# yetisponder_vesp02_2_2.net
KiCad netlist of a schematic drawn in EAGLE
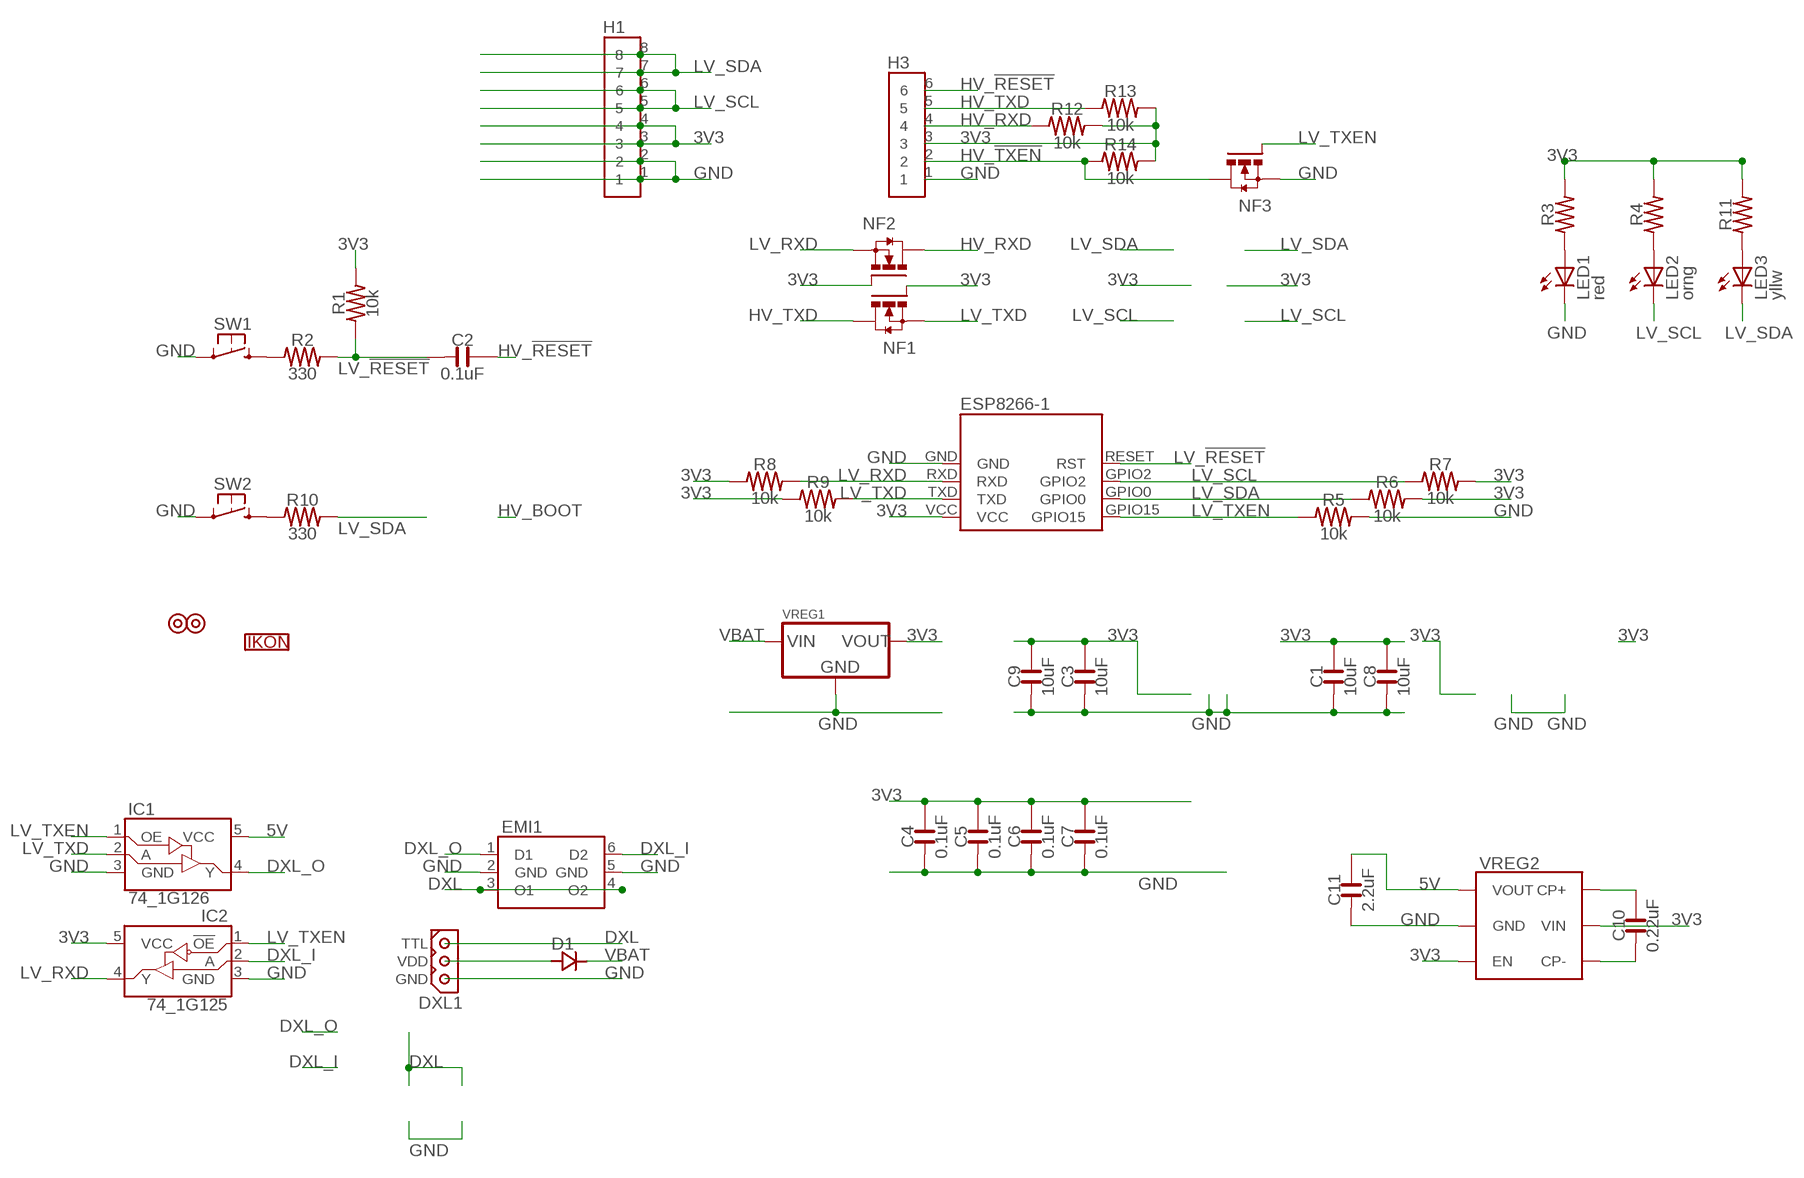
[diagram p0: schematic, sheet 1]

(export (version "E")
  (design (tool "Eeschema 10.0.6"))
  (components
    (comp (ref "C1")
      (value "10uF")
      (footprint "eagle-import:0805_YAGEO")
      (libsource (lib "eagle-import") (part "CAPACITOR-0805"))
    )
    (comp (ref "C2")
      (value "0.1uF")
      (footprint "eagle-import:0402_YAGEO")
      (libsource (lib "eagle-import") (part "CAPACITOR-0402"))
    )
    (comp (ref "C3")
      (value "10uF")
      (footprint "eagle-import:0805_YAGEO")
      (libsource (lib "eagle-import") (part "CAPACITOR-0805"))
    )
    (comp (ref "C4")
      (value "0.1uF")
      (footprint "eagle-import:0402_YAGEO")
      (libsource (lib "eagle-import") (part "CAPACITOR-0402"))
    )
    (comp (ref "C5")
      (value "0.1uF")
      (footprint "eagle-import:0402_YAGEO")
      (libsource (lib "eagle-import") (part "CAPACITOR-0402"))
    )
    (comp (ref "C6")
      (value "0.1uF")
      (footprint "eagle-import:0402_YAGEO")
      (libsource (lib "eagle-import") (part "CAPACITOR-0402"))
    )
    (comp (ref "C7")
      (value "0.1uF")
      (footprint "eagle-import:0402_YAGEO")
      (libsource (lib "eagle-import") (part "CAPACITOR-0402"))
    )
    (comp (ref "C8")
      (value "10uF")
      (footprint "eagle-import:0805_YAGEO")
      (libsource (lib "eagle-import") (part "CAPACITOR-0805"))
    )
    (comp (ref "C9")
      (value "10uF")
      (footprint "eagle-import:0805_YAGEO")
      (libsource (lib "eagle-import") (part "CAPACITOR-0805"))
    )
    (comp (ref "C10")
      (value "0.22uF")
      (footprint "eagle-import:0402_YAGEO")
      (libsource (lib "eagle-import") (part "CAPACITOR-0402"))
    )
    (comp (ref "C11")
      (value "2.2uF")
      (footprint "eagle-import:0402_YAGEO")
      (libsource (lib "eagle-import") (part "CAPACITOR-0402"))
    )
    (comp (ref "D1")
      (value "DIODE_RECTIFIER-POWER-DI5")
      (footprint "eagle-import:POWER-DI5")
      (libsource (lib "eagle-import") (part "DIODE_RECTIFIER-POWER-DI5"))
    )
    (comp (ref "DXL1")
      (value "DXL_TTL-V")
      (footprint "eagle-import:MOLEX_5267-3")
      (libsource (lib "eagle-import") (part "DXL_TTL-V"))
    )
    (comp (ref "EMI1")
      (value "EMI_2CH")
      (footprint "eagle-import:SOT-563")
      (libsource (lib "eagle-import") (part "EMI_2CH"))
    )
    (comp (ref "ESP8266-1")
      (value "ESP8266-02")
      (footprint "eagle-import:ESP8266-02")
      (libsource (lib "eagle-import") (part "ESP8266-02"))
    )
    (comp (ref "H1")
      (value "HEADER_8P-0.1\"_2X4-SMD-SULLINS")
      (footprint "eagle-import:HEADER-0.1__2X4-SMD-SULLINS")
      (libsource (lib "eagle-import") (part "HEADER_8P-0.1{dblquote}_2X4-SMD-SULLINS"))
    )
    (comp (ref "H3")
      (value "HEADER_6P-0.1\"")
      (footprint "eagle-import:HEADER-0.1__1X6")
      (libsource (lib "eagle-import") (part "HEADER_6P-0.1{dblquote}"))
    )
    (comp (ref "IC1")
      (value "LOGIC_74_1G126-DCK")
      (footprint "eagle-import:DCK(R-PDSO-G5)_SC70")
      (libsource (lib "eagle-import") (part "LOGIC_74_1G126-DCK"))
    )
    (comp (ref "IC2")
      (value "LOGIC_74_1G125-DCK")
      (footprint "eagle-import:DCK(R-PDSO-G5)_SC70")
      (libsource (lib "eagle-import") (part "LOGIC_74_1G125-DCK"))
    )
    (comp (ref "IKON1")
      (value "IKON-VERSACOMA-5")
      (footprint "eagle-import:IKON_VERSACOMA_5MM")
      (libsource (lib "eagle-import") (part "IKON-VERSACOMA-5"))
    )
    (comp (ref "LED1")
      (value "red")
      (footprint "eagle-import:0402_LED")
      (libsource (lib "eagle-import") (part "LED-0402"))
    )
    (comp (ref "LED2")
      (value "orng")
      (footprint "eagle-import:0402_LED")
      (libsource (lib "eagle-import") (part "LED-0402"))
    )
    (comp (ref "LED3")
      (value "yllw")
      (footprint "eagle-import:0402_LED")
      (libsource (lib "eagle-import") (part "LED-0402"))
    )
    (comp (ref "NF1")
      (value "FET_N-CH-SOT-23-3")
      (footprint "eagle-import:SOT-23-3")
      (libsource (lib "eagle-import") (part "FET_N-CH-SOT-23-3"))
    )
    (comp (ref "NF2")
      (value "FET_N-CH-SOT-23-3")
      (footprint "eagle-import:SOT-23-3")
      (libsource (lib "eagle-import") (part "FET_N-CH-SOT-23-3"))
    )
    (comp (ref "NF3")
      (value "FET_N-CH-SOT-23-3")
      (footprint "eagle-import:SOT-23-3")
      (libsource (lib "eagle-import") (part "FET_N-CH-SOT-23-3"))
    )
    (comp (ref "R1")
      (value "10k")
      (footprint "eagle-import:0402_YAGEO")
      (libsource (lib "eagle-import") (part "RESISTOR-0402"))
    )
    (comp (ref "R2")
      (value "330")
      (footprint "eagle-import:0402_YAGEO")
      (libsource (lib "eagle-import") (part "RESISTOR-0402"))
    )
    (comp (ref "R3")
      (value "RESISTOR-0402")
      (footprint "eagle-import:0402_YAGEO")
      (libsource (lib "eagle-import") (part "RESISTOR-0402"))
    )
    (comp (ref "R4")
      (value "RESISTOR-0402")
      (footprint "eagle-import:0402_YAGEO")
      (libsource (lib "eagle-import") (part "RESISTOR-0402"))
    )
    (comp (ref "R5")
      (value "10k")
      (footprint "eagle-import:0402_YAGEO")
      (libsource (lib "eagle-import") (part "RESISTOR-0402"))
    )
    (comp (ref "R6")
      (value "10k")
      (footprint "eagle-import:0402_YAGEO")
      (libsource (lib "eagle-import") (part "RESISTOR-0402"))
    )
    (comp (ref "R7")
      (value "10k")
      (footprint "eagle-import:0402_YAGEO")
      (libsource (lib "eagle-import") (part "RESISTOR-0402"))
    )
    (comp (ref "R8")
      (value "10k")
      (footprint "eagle-import:0402_YAGEO")
      (libsource (lib "eagle-import") (part "RESISTOR-0402"))
    )
    (comp (ref "R9")
      (value "10k")
      (footprint "eagle-import:0402_YAGEO")
      (libsource (lib "eagle-import") (part "RESISTOR-0402"))
    )
    (comp (ref "R10")
      (value "330")
      (footprint "eagle-import:0402_YAGEO")
      (libsource (lib "eagle-import") (part "RESISTOR-0402"))
    )
    (comp (ref "R11")
      (value "RESISTOR-0402")
      (footprint "eagle-import:0402_YAGEO")
      (libsource (lib "eagle-import") (part "RESISTOR-0402"))
    )
    (comp (ref "R12")
      (value "10k")
      (footprint "eagle-import:0402_YAGEO")
      (libsource (lib "eagle-import") (part "RESISTOR-0402"))
    )
    (comp (ref "R13")
      (value "10k")
      (footprint "eagle-import:0402_YAGEO")
      (libsource (lib "eagle-import") (part "RESISTOR-0402"))
    )
    (comp (ref "R14")
      (value "10k")
      (footprint "eagle-import:0402_YAGEO")
      (libsource (lib "eagle-import") (part "RESISTOR-0402"))
    )
    (comp (ref "S1")
      (value "METRIC_SCREWS-M2.5_T")
      (footprint "eagle-import:M2.5_SCREW_TENTED")
      (libsource (lib "eagle-import") (part "METRIC_SCREWS-M2.5_T"))
    )
    (comp (ref "S2")
      (value "METRIC_SCREWS-M2.5_T")
      (footprint "eagle-import:M2.5_SCREW_TENTED")
      (libsource (lib "eagle-import") (part "METRIC_SCREWS-M2.5_T"))
    )
    (comp (ref "SW1")
      (value "SWITCH_SPST-6MMX6MM-PTH")
      (footprint "eagle-import:SWITCH_TE_1825910-7")
      (libsource (lib "eagle-import") (part "SWITCH_SPST-6MMX6MM-PTH"))
    )
    (comp (ref "SW2")
      (value "SWITCH_SPST-6MMX6MM-PTH")
      (footprint "eagle-import:SWITCH_TE_1825910-7")
      (libsource (lib "eagle-import") (part "SWITCH_SPST-6MMX6MM-PTH"))
    )
    (comp (ref "VREG1")
      (value "VREG_78XX-OKI-78SR-H")
      (footprint "eagle-import:VREG-OKI-78SR-H")
      (libsource (lib "eagle-import") (part "VREG_78XX-OKI-78SR-H"))
    )
    (comp (ref "VREG2")
      (value "VREG_REG710XX")
      (footprint "eagle-import:SOT-23-6")
      (libsource (lib "eagle-import") (part "VREG_REG710XX"))
    )
  )
  (nets
    (net (code "1") (name "/3V3") (class "Default")
      (node (ref "C1") (pin "2") (pinfunction "P$2_2") (pintype "passive"))
      (node (ref "C3") (pin "2") (pinfunction "P$2_2") (pintype "passive"))
      (node (ref "C4") (pin "2") (pinfunction "P$2_2") (pintype "passive"))
      (node (ref "C5") (pin "2") (pinfunction "P$2_2") (pintype "passive"))
      (node (ref "C6") (pin "2") (pinfunction "P$2_2") (pintype "passive"))
      (node (ref "C7") (pin "2") (pinfunction "P$2_2") (pintype "passive"))
      (node (ref "C8") (pin "2") (pinfunction "P$2_2") (pintype "passive"))
      (node (ref "C9") (pin "2") (pinfunction "P$2_2") (pintype "passive"))
      (node (ref "ESP8266-1") (pin "VCC") (pinfunction "VCC_VCC") (pintype "bidirectional"))
      (node (ref "H1") (pin "3") (pinfunction "3_3") (pintype "bidirectional"))
      (node (ref "H1") (pin "4") (pinfunction "4_4") (pintype "bidirectional"))
      (node (ref "H3") (pin "3") (pinfunction "3_3") (pintype "bidirectional"))
      (node (ref "IC2") (pin "5") (pinfunction "VCC_5") (pintype "bidirectional"))
      (node (ref "NF1") (pin "1G") (pinfunction "G_1G") (pintype "passive"))
      (node (ref "NF2") (pin "1G") (pinfunction "G_1G") (pintype "passive"))
      (node (ref "R1") (pin "2") (pinfunction "2_2") (pintype "passive"))
      (node (ref "R11") (pin "2") (pinfunction "2_2") (pintype "passive"))
      (node (ref "R12") (pin "2") (pinfunction "2_2") (pintype "passive"))
      (node (ref "R13") (pin "2") (pinfunction "2_2") (pintype "passive"))
      (node (ref "R14") (pin "2") (pinfunction "2_2") (pintype "passive"))
      (node (ref "R3") (pin "2") (pinfunction "2_2") (pintype "passive"))
      (node (ref "R4") (pin "2") (pinfunction "2_2") (pintype "passive"))
      (node (ref "R6") (pin "2") (pinfunction "2_2") (pintype "passive"))
      (node (ref "R7") (pin "2") (pinfunction "2_2") (pintype "passive"))
      (node (ref "R8") (pin "1") (pinfunction "1_1") (pintype "passive"))
      (node (ref "R9") (pin "1") (pinfunction "1_1") (pintype "passive"))
      (node (ref "VREG1") (pin "3") (pinfunction "VOUT_3") (pintype "bidirectional"))
      (node (ref "VREG2") (pin "3") (pinfunction "EN_3") (pintype "bidirectional"))
      (node (ref "VREG2") (pin "5") (pinfunction "VIN_5") (pintype "bidirectional"))
    )
    (net (code "2") (name "/5V") (class "Default")
      (node (ref "C11") (pin "2") (pinfunction "P$2_2") (pintype "passive"))
      (node (ref "IC1") (pin "5") (pinfunction "VCC_5") (pintype "bidirectional"))
      (node (ref "VREG2") (pin "1") (pinfunction "VOUT_1") (pintype "bidirectional"))
    )
    (net (code "3") (name "/DXL") (class "Default")
      (node (ref "DXL1") (pin "1") (pinfunction "TTL_1") (pintype "bidirectional"))
      (node (ref "EMI1") (pin "3") (pinfunction "O1_3") (pintype "bidirectional"))
      (node (ref "EMI1") (pin "4") (pinfunction "O2_4") (pintype "bidirectional"))
    )
    (net (code "4") (name "/DXL_I") (class "Default")
      (node (ref "EMI1") (pin "6") (pinfunction "D2_6") (pintype "bidirectional"))
      (node (ref "IC2") (pin "2") (pinfunction "A_2") (pintype "bidirectional"))
    )
    (net (code "5") (name "/DXL_O") (class "Default")
      (node (ref "EMI1") (pin "1") (pinfunction "D1_1") (pintype "bidirectional"))
      (node (ref "IC1") (pin "4") (pinfunction "Y_4") (pintype "bidirectional"))
    )
    (net (code "6") (name "/GND") (class "Default")
      (node (ref "C1") (pin "1") (pinfunction "P$1_1") (pintype "passive"))
      (node (ref "C11") (pin "1") (pinfunction "P$1_1") (pintype "passive"))
      (node (ref "C3") (pin "1") (pinfunction "P$1_1") (pintype "passive"))
      (node (ref "C4") (pin "1") (pinfunction "P$1_1") (pintype "passive"))
      (node (ref "C5") (pin "1") (pinfunction "P$1_1") (pintype "passive"))
      (node (ref "C6") (pin "1") (pinfunction "P$1_1") (pintype "passive"))
      (node (ref "C7") (pin "1") (pinfunction "P$1_1") (pintype "passive"))
      (node (ref "C8") (pin "1") (pinfunction "P$1_1") (pintype "passive"))
      (node (ref "C9") (pin "1") (pinfunction "P$1_1") (pintype "passive"))
      (node (ref "DXL1") (pin "3") (pinfunction "GND_3") (pintype "bidirectional"))
      (node (ref "EMI1") (pin "2") (pinfunction "GND_2") (pintype "bidirectional"))
      (node (ref "EMI1") (pin "5") (pinfunction "GND_5") (pintype "bidirectional"))
      (node (ref "ESP8266-1") (pin "GND") (pinfunction "GND_GND") (pintype "bidirectional"))
      (node (ref "H1") (pin "1") (pinfunction "1_1") (pintype "bidirectional"))
      (node (ref "H1") (pin "2") (pinfunction "2_2") (pintype "bidirectional"))
      (node (ref "H3") (pin "1") (pinfunction "1_1") (pintype "bidirectional"))
      (node (ref "IC1") (pin "3") (pinfunction "GND_3") (pintype "bidirectional"))
      (node (ref "IC2") (pin "3") (pinfunction "GND_3") (pintype "bidirectional"))
      (node (ref "LED1") (pin "C") (pinfunction "C_C") (pintype "passive"))
      (node (ref "NF3") (pin "2S") (pinfunction "S_2S") (pintype "passive"))
      (node (ref "R5") (pin "2") (pinfunction "2_2") (pintype "passive"))
      (node (ref "SW1") (pin "2@1") (pinfunction "2_2@1") (pintype "passive"))
      (node (ref "SW1") (pin "2@2") (pinfunction "2_2@2") (pintype "passive"))
      (node (ref "SW2") (pin "2@1") (pinfunction "2_2@1") (pintype "passive"))
      (node (ref "SW2") (pin "2@2") (pinfunction "2_2@2") (pintype "passive"))
      (node (ref "VREG1") (pin "2") (pinfunction "GND_2") (pintype "bidirectional"))
      (node (ref "VREG2") (pin "2") (pinfunction "GND_2") (pintype "bidirectional"))
    )
    (net (code "8") (name "/HV_RXD") (class "Default")
      (node (ref "H3") (pin "4") (pinfunction "4_4") (pintype "bidirectional"))
      (node (ref "NF2") (pin "3D") (pinfunction "D_3D") (pintype "passive"))
      (node (ref "R12") (pin "1") (pinfunction "1_1") (pintype "passive"))
    )
    (net (code "9") (name "/HV_TXD") (class "Default")
      (node (ref "H3") (pin "5") (pinfunction "5_5") (pintype "bidirectional"))
      (node (ref "NF1") (pin "3D") (pinfunction "D_3D") (pintype "passive"))
      (node (ref "R13") (pin "1") (pinfunction "1_1") (pintype "passive"))
    )
    (net (code "10") (name "/HV_~{RESET}") (class "Default")
      (node (ref "C2") (pin "2") (pinfunction "P$2_2") (pintype "passive"))
      (node (ref "H3") (pin "6") (pinfunction "6_6") (pintype "bidirectional"))
    )
    (net (code "11") (name "/HV_~{TXEN}") (class "Default")
      (node (ref "H3") (pin "2") (pinfunction "2_2") (pintype "bidirectional"))
      (node (ref "NF3") (pin "3D") (pinfunction "D_3D") (pintype "passive"))
      (node (ref "R14") (pin "1") (pinfunction "1_1") (pintype "passive"))
    )
    (net (code "12") (name "/LV_RXD") (class "Default")
      (node (ref "ESP8266-1") (pin "RXD") (pinfunction "RXD_RXD") (pintype "bidirectional"))
      (node (ref "IC2") (pin "4") (pinfunction "Y_4") (pintype "bidirectional"))
      (node (ref "NF2") (pin "2S") (pinfunction "S_2S") (pintype "passive"))
      (node (ref "R8") (pin "2") (pinfunction "2_2") (pintype "passive"))
    )
    (net (code "13") (name "/LV_SCL") (class "Default")
      (node (ref "ESP8266-1") (pin "GPIO2") (pinfunction "GPIO2_GPIO2") (pintype "bidirectional"))
      (node (ref "H1") (pin "5") (pinfunction "5_5") (pintype "bidirectional"))
      (node (ref "H1") (pin "6") (pinfunction "6_6") (pintype "bidirectional"))
      (node (ref "LED2") (pin "C") (pinfunction "C_C") (pintype "passive"))
      (node (ref "R7") (pin "1") (pinfunction "1_1") (pintype "passive"))
    )
    (net (code "14") (name "/LV_SDA") (class "Default")
      (node (ref "ESP8266-1") (pin "GPIO0") (pinfunction "GPIO0_GPIO0") (pintype "bidirectional"))
      (node (ref "H1") (pin "7") (pinfunction "7_7") (pintype "bidirectional"))
      (node (ref "H1") (pin "8") (pinfunction "8_8") (pintype "bidirectional"))
      (node (ref "LED3") (pin "C") (pinfunction "C_C") (pintype "passive"))
      (node (ref "R10") (pin "2") (pinfunction "2_2") (pintype "passive"))
      (node (ref "R6") (pin "1") (pinfunction "1_1") (pintype "passive"))
    )
    (net (code "15") (name "/LV_TXD") (class "Default")
      (node (ref "ESP8266-1") (pin "TXD") (pinfunction "TXD_TXD") (pintype "bidirectional"))
      (node (ref "IC1") (pin "2") (pinfunction "A_2") (pintype "bidirectional"))
      (node (ref "NF1") (pin "2S") (pinfunction "S_2S") (pintype "passive"))
      (node (ref "R9") (pin "2") (pinfunction "2_2") (pintype "passive"))
    )
    (net (code "16") (name "/LV_TXEN") (class "Default")
      (node (ref "ESP8266-1") (pin "GPIO15") (pinfunction "GPIO15_GPIO15") (pintype "bidirectional"))
      (node (ref "IC1") (pin "1") (pinfunction "OE_1") (pintype "bidirectional"))
      (node (ref "IC2") (pin "1") (pinfunction "~{OE}_1") (pintype "bidirectional"))
      (node (ref "NF3") (pin "1G") (pinfunction "G_1G") (pintype "passive"))
      (node (ref "R5") (pin "1") (pinfunction "1_1") (pintype "passive"))
    )
    (net (code "17") (name "/LV_~{RESET}") (class "Default")
      (node (ref "C2") (pin "1") (pinfunction "P$1_1") (pintype "passive"))
      (node (ref "ESP8266-1") (pin "RESET") (pinfunction "RST_RESET") (pintype "bidirectional"))
      (node (ref "R1") (pin "1") (pinfunction "1_1") (pintype "passive"))
      (node (ref "R2") (pin "2") (pinfunction "2_2") (pintype "passive"))
    )
    (net (code "18") (name "/VBAT") (class "Default")
      (node (ref "D1") (pin "PAD") (pinfunction "C_PAD") (pintype "bidirectional"))
      (node (ref "VREG1") (pin "1") (pinfunction "VIN_1") (pintype "bidirectional"))
    )
    (net (code "19") (name "Net-(C10-P$1)") (class "Default")
      (node (ref "C10") (pin "1") (pinfunction "P$1_1") (pintype "passive"))
      (node (ref "VREG2") (pin "4") (pinfunction "CP-_4") (pintype "bidirectional"))
    )
    (net (code "20") (name "Net-(C10-P$2)") (class "Default")
      (node (ref "C10") (pin "2") (pinfunction "P$2_2") (pintype "passive"))
      (node (ref "VREG2") (pin "6") (pinfunction "CP+_6") (pintype "bidirectional"))
    )
    (net (code "21") (name "Net-(DXL1-VDD)") (class "Default")
      (node (ref "D1") (pin "LEFT") (pinfunction "A_LEFT") (pintype "bidirectional"))
      (node (ref "D1") (pin "RIGHT") (pinfunction "A_RIGHT") (pintype "bidirectional"))
      (node (ref "DXL1") (pin "2") (pinfunction "VDD_2") (pintype "bidirectional"))
    )
    (net (code "22") (name "Net-(LED1-PadA)") (class "Default")
      (node (ref "LED1") (pin "A") (pinfunction "A_A") (pintype "passive"))
      (node (ref "R3") (pin "1") (pinfunction "1_1") (pintype "passive"))
    )
    (net (code "23") (name "Net-(LED2-PadA)") (class "Default")
      (node (ref "LED2") (pin "A") (pinfunction "A_A") (pintype "passive"))
      (node (ref "R4") (pin "1") (pinfunction "1_1") (pintype "passive"))
    )
    (net (code "24") (name "Net-(LED3-PadA)") (class "Default")
      (node (ref "LED3") (pin "A") (pinfunction "A_A") (pintype "passive"))
      (node (ref "R11") (pin "1") (pinfunction "1_1") (pintype "passive"))
    )
    (net (code "25") (name "Net-(R2-Pad1)") (class "Default")
      (node (ref "R2") (pin "1") (pinfunction "1_1") (pintype "passive"))
      (node (ref "SW1") (pin "1@1") (pinfunction "1_1@1") (pintype "passive"))
      (node (ref "SW1") (pin "1@2") (pinfunction "1_1@2") (pintype "passive"))
    )
    (net (code "26") (name "Net-(R10-Pad1)") (class "Default")
      (node (ref "R10") (pin "1") (pinfunction "1_1") (pintype "passive"))
      (node (ref "SW2") (pin "1@1") (pinfunction "1_1@1") (pintype "passive"))
      (node (ref "SW2") (pin "1@2") (pinfunction "1_1@2") (pintype "passive"))
    )
    (net (code "27") (name "unconnected-(S1-PadP$1)") (class "Default")
      (node (ref "S1") (pin "P$1") (pinfunction "P$1_P$1") (pintype "passive"))
    )
    (net (code "28") (name "unconnected-(S2-PadP$1)") (class "Default")
      (node (ref "S2") (pin "P$1") (pinfunction "P$1_P$1") (pintype "passive"))
    )
  )
)
